# LCD_Adapter_Board.net
KiCad netlist of a schematic drawn in EAGLE
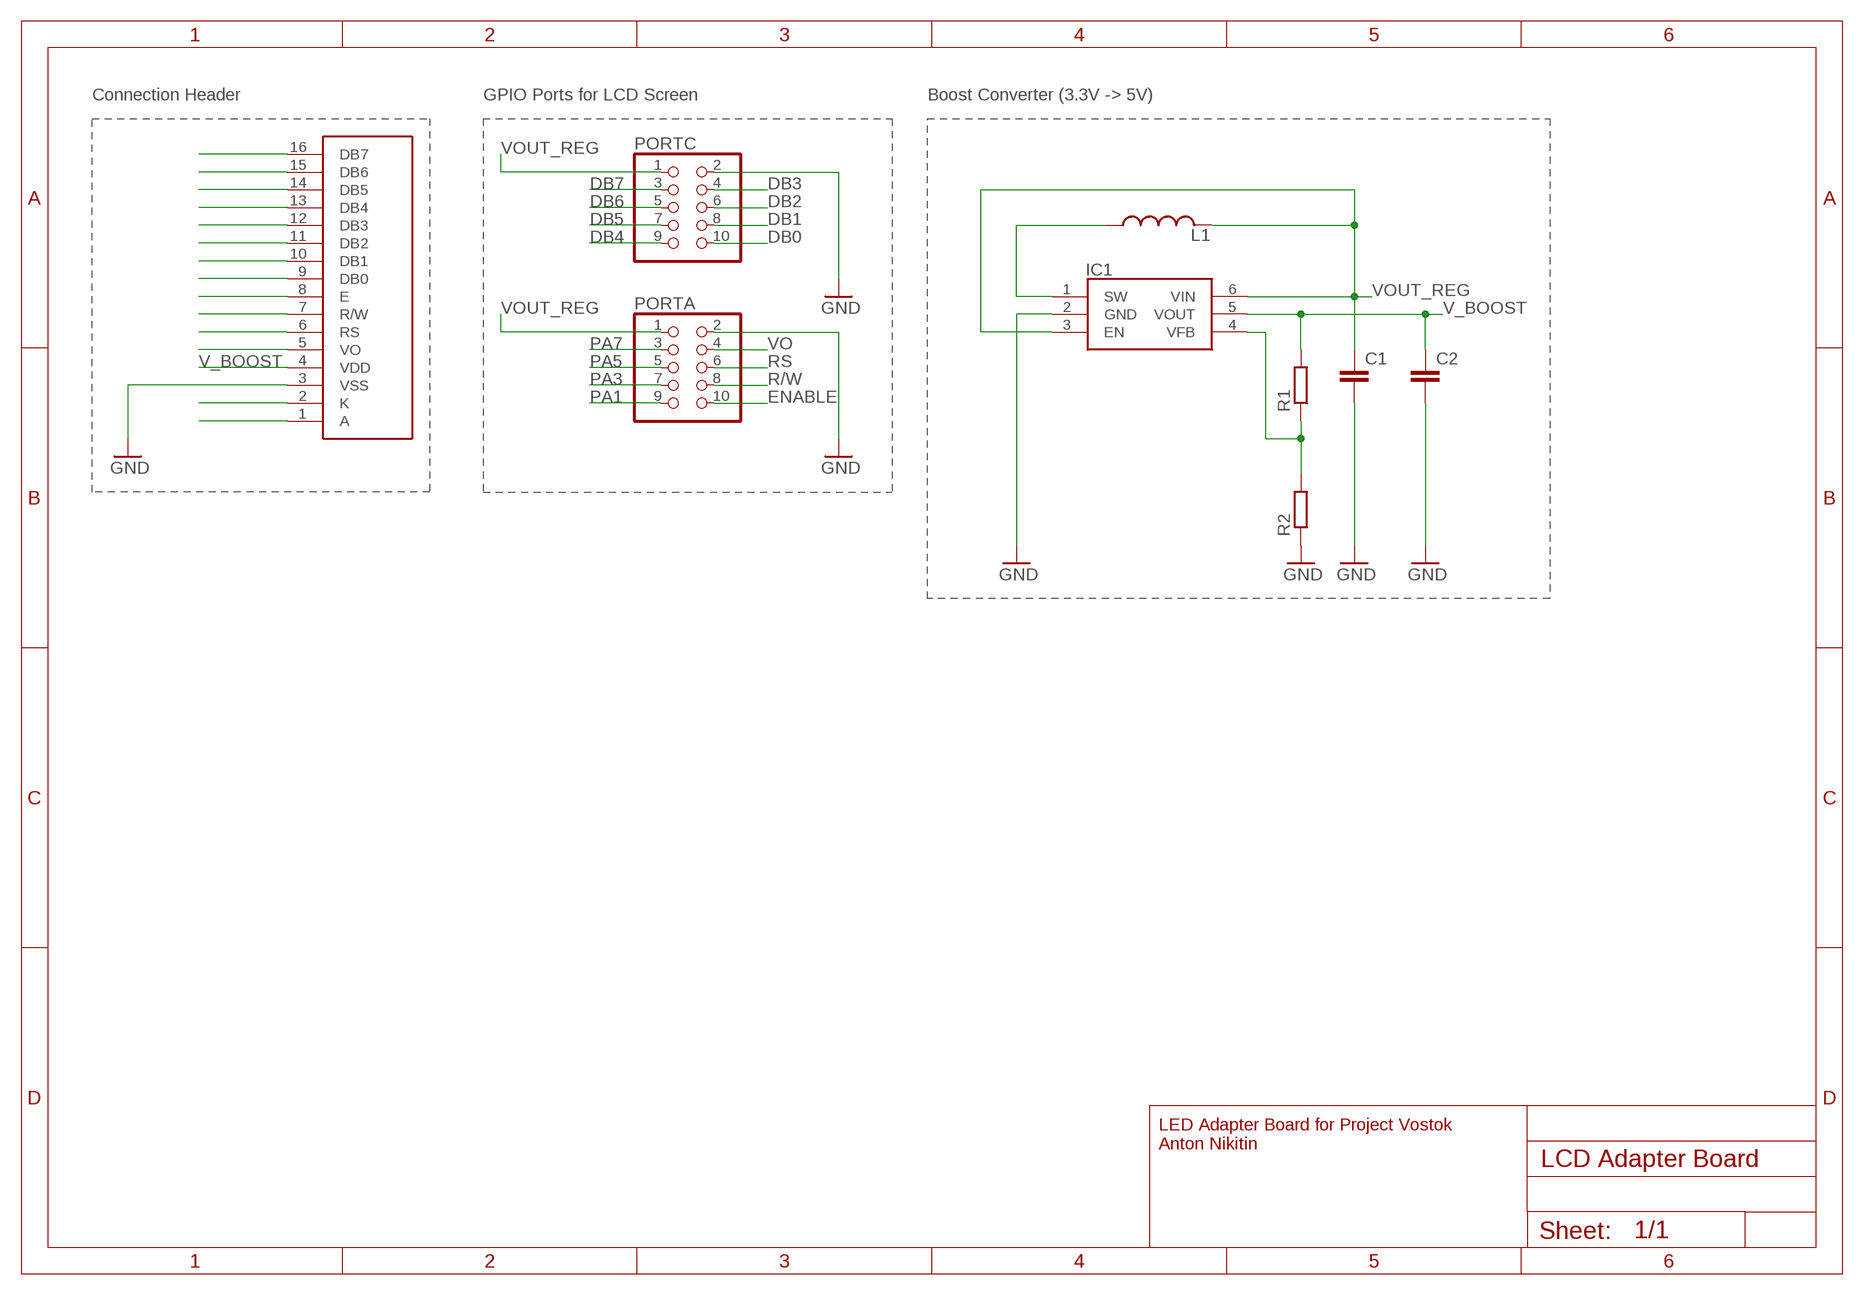
[diagram p0: schematic, sheet 1]

(export (version "E")
  (design (tool "Eeschema 10.0.6"))
  (components
    (comp (ref "C1")
      (value "C-EUC0603")
      (footprint "eagle-import:C0603")
      (libsource (lib "eagle-import") (part "C-EUC0603"))
    )
    (comp (ref "C2")
      (value "C-EUC0603")
      (footprint "eagle-import:C0603")
      (libsource (lib "eagle-import") (part "C-EUC0603"))
    )
    (comp (ref "DS1")
      (value "162B-CC-BC-3LP")
      (footprint "eagle-import:162B")
      (fields (field (name "RS_PART_NUMBER") "5326385"))
      (libsource (lib "eagle-import") (part "162B-CC-BC-3LP"))
    )
    (comp (ref "IC1")
      (value "MCP1640BT-I_CHY")
      (footprint "eagle-import:SOT95P270X145-6N")
      (fields
        (field (name "MANUFACTURER_PART_NUMBER") "MCP1640BT-I/CHY")
        (field (name "MOUSER_PART_NUMBER") "579-MCP1640BT-I/CHY")
        (field (name "RS_PART_NUMBER") "7386250P")
      )
      (libsource (lib "eagle-import") (part "MCP1640BT-I_CHY"))
    )
    (comp (ref "L1")
      (value "L-USL0201")
      (footprint "eagle-import:L0201")
      (libsource (lib "eagle-import") (part "L-USL0201"))
    )
    (comp (ref "PORTA")
      (value "PINHD-2X5")
      (footprint "eagle-import:2X05")
      (libsource (lib "eagle-import") (part "PINHD-2X5"))
    )
    (comp (ref "PORTC")
      (value "PINHD-2X5")
      (footprint "eagle-import:2X05")
      (libsource (lib "eagle-import") (part "PINHD-2X5"))
    )
    (comp (ref "R1")
      (value "R-EU_R0603")
      (footprint "eagle-import:R0603")
      (libsource (lib "eagle-import") (part "R-EU_R0603"))
    )
    (comp (ref "R2")
      (value "R-EU_R0603")
      (footprint "eagle-import:R0603")
      (libsource (lib "eagle-import") (part "R-EU_R0603"))
    )
  )
  (nets
    (net (code "1") (name "/DB0") (class "Default")
      (node (ref "PORTC") (pin "10") (pinfunction "10_10") (pintype "passive"))
    )
    (net (code "2") (name "/DB1") (class "Default")
      (node (ref "PORTC") (pin "8") (pinfunction "8_8") (pintype "passive"))
    )
    (net (code "3") (name "/DB2") (class "Default")
      (node (ref "PORTC") (pin "6") (pinfunction "6_6") (pintype "passive"))
    )
    (net (code "4") (name "/DB3") (class "Default")
      (node (ref "PORTC") (pin "4") (pinfunction "4_4") (pintype "passive"))
    )
    (net (code "5") (name "/DB4") (class "Default")
      (node (ref "PORTC") (pin "9") (pinfunction "9_9") (pintype "passive"))
    )
    (net (code "6") (name "/DB5") (class "Default")
      (node (ref "PORTC") (pin "7") (pinfunction "7_7") (pintype "passive"))
    )
    (net (code "7") (name "/DB6") (class "Default")
      (node (ref "PORTC") (pin "5") (pinfunction "5_5") (pintype "passive"))
    )
    (net (code "8") (name "/DB7") (class "Default")
      (node (ref "PORTC") (pin "3") (pinfunction "3_3") (pintype "passive"))
    )
    (net (code "9") (name "/ENABLE") (class "Default")
      (node (ref "PORTA") (pin "10") (pinfunction "10_10") (pintype "passive"))
    )
    (net (code "10") (name "/PA1") (class "Default")
      (node (ref "PORTA") (pin "9") (pinfunction "9_9") (pintype "passive"))
    )
    (net (code "11") (name "/PA3") (class "Default")
      (node (ref "PORTA") (pin "7") (pinfunction "7_7") (pintype "passive"))
    )
    (net (code "12") (name "/PA5") (class "Default")
      (node (ref "PORTA") (pin "5") (pinfunction "5_5") (pintype "passive"))
    )
    (net (code "13") (name "/PA7") (class "Default")
      (node (ref "PORTA") (pin "3") (pinfunction "3_3") (pintype "passive"))
    )
    (net (code "14") (name "/RS") (class "Default")
      (node (ref "PORTA") (pin "6") (pinfunction "6_6") (pintype "passive"))
    )
    (net (code "15") (name "/R{slash}W") (class "Default")
      (node (ref "PORTA") (pin "8") (pinfunction "8_8") (pintype "passive"))
    )
    (net (code "16") (name "/VO") (class "Default")
      (node (ref "PORTA") (pin "4") (pinfunction "4_4") (pintype "passive"))
    )
    (net (code "17") (name "/VOUT_REG") (class "Default")
      (node (ref "C1") (pin "1") (pinfunction "1_1") (pintype "passive"))
      (node (ref "IC1") (pin "3") (pinfunction "EN_3") (pintype "bidirectional"))
      (node (ref "IC1") (pin "6") (pinfunction "VIN_6") (pintype "input"))
      (node (ref "L1") (pin "2") (pinfunction "2_2") (pintype "passive"))
      (node (ref "PORTA") (pin "1") (pinfunction "1_1") (pintype "passive"))
      (node (ref "PORTC") (pin "1") (pinfunction "1_1") (pintype "passive"))
    )
    (net (code "18") (name "/V_BOOST") (class "Default")
      (node (ref "C2") (pin "1") (pinfunction "1_1") (pintype "passive"))
      (node (ref "DS1") (pin "4") (pinfunction "VDD_4") (pintype "bidirectional"))
      (node (ref "IC1") (pin "5") (pinfunction "VOUT_5") (pintype "output"))
      (node (ref "R1") (pin "2") (pinfunction "2_2") (pintype "passive"))
    )
    (net (code "19") (name "GND") (class "Default")
      (node (ref "C1") (pin "2") (pinfunction "2_2") (pintype "passive"))
      (node (ref "C2") (pin "2") (pinfunction "2_2") (pintype "passive"))
      (node (ref "DS1") (pin "3") (pinfunction "VSS_3") (pintype "bidirectional"))
      (node (ref "IC1") (pin "2") (pinfunction "GND_2") (pintype "power_in"))
      (node (ref "PORTA") (pin "2") (pinfunction "2_2") (pintype "passive"))
      (node (ref "PORTC") (pin "2") (pinfunction "2_2") (pintype "passive"))
      (node (ref "R2") (pin "1") (pinfunction "1_1") (pintype "passive"))
    )
    (net (code "20") (name "Net-(IC1-SW)") (class "Default")
      (node (ref "IC1") (pin "1") (pinfunction "SW_1") (pintype "bidirectional"))
      (node (ref "L1") (pin "1") (pinfunction "1_1") (pintype "passive"))
    )
    (net (code "21") (name "Net-(IC1-VFB)") (class "Default")
      (node (ref "IC1") (pin "4") (pinfunction "VFB_4") (pintype "bidirectional"))
      (node (ref "R1") (pin "1") (pinfunction "1_1") (pintype "passive"))
      (node (ref "R2") (pin "2") (pinfunction "2_2") (pintype "passive"))
    )
    (net (code "22") (name "unconnected-(DS1-A-Pad1)") (class "Default")
      (node (ref "DS1") (pin "1") (pinfunction "A_1") (pintype "bidirectional"))
    )
    (net (code "23") (name "unconnected-(DS1-DB0-Pad9)") (class "Default")
      (node (ref "DS1") (pin "9") (pinfunction "DB0_9") (pintype "bidirectional"))
    )
    (net (code "24") (name "unconnected-(DS1-DB1-Pad10)") (class "Default")
      (node (ref "DS1") (pin "10") (pinfunction "DB1_10") (pintype "bidirectional"))
    )
    (net (code "25") (name "unconnected-(DS1-DB2-Pad11)") (class "Default")
      (node (ref "DS1") (pin "11") (pinfunction "DB2_11") (pintype "bidirectional"))
    )
    (net (code "26") (name "unconnected-(DS1-DB3-Pad12)") (class "Default")
      (node (ref "DS1") (pin "12") (pinfunction "DB3_12") (pintype "bidirectional"))
    )
    (net (code "27") (name "unconnected-(DS1-DB4-Pad13)") (class "Default")
      (node (ref "DS1") (pin "13") (pinfunction "DB4_13") (pintype "bidirectional"))
    )
    (net (code "28") (name "unconnected-(DS1-DB5-Pad14)") (class "Default")
      (node (ref "DS1") (pin "14") (pinfunction "DB5_14") (pintype "bidirectional"))
    )
    (net (code "29") (name "unconnected-(DS1-DB6-Pad15)") (class "Default")
      (node (ref "DS1") (pin "15") (pinfunction "DB6_15") (pintype "bidirectional"))
    )
    (net (code "30") (name "unconnected-(DS1-DB7-Pad16)") (class "Default")
      (node (ref "DS1") (pin "16") (pinfunction "DB7_16") (pintype "bidirectional"))
    )
    (net (code "31") (name "unconnected-(DS1-E-Pad8)") (class "Default")
      (node (ref "DS1") (pin "8") (pinfunction "E_8") (pintype "bidirectional"))
    )
    (net (code "32") (name "unconnected-(DS1-K-Pad2)") (class "Default")
      (node (ref "DS1") (pin "2") (pinfunction "K_2") (pintype "bidirectional"))
    )
    (net (code "33") (name "unconnected-(DS1-RS-Pad6)") (class "Default")
      (node (ref "DS1") (pin "6") (pinfunction "RS_6") (pintype "bidirectional"))
    )
    (net (code "34") (name "unconnected-(DS1-R{slash}W-Pad7)") (class "Default")
      (node (ref "DS1") (pin "7") (pinfunction "R/W_7") (pintype "bidirectional"))
    )
    (net (code "35") (name "unconnected-(DS1-VO-Pad5)") (class "Default")
      (node (ref "DS1") (pin "5") (pinfunction "VO_5") (pintype "bidirectional"))
    )
  )
)
